# Sensor_Al_Fatih_Multiplekser_Baru.net
KiCad netlist of a schematic drawn in EAGLE
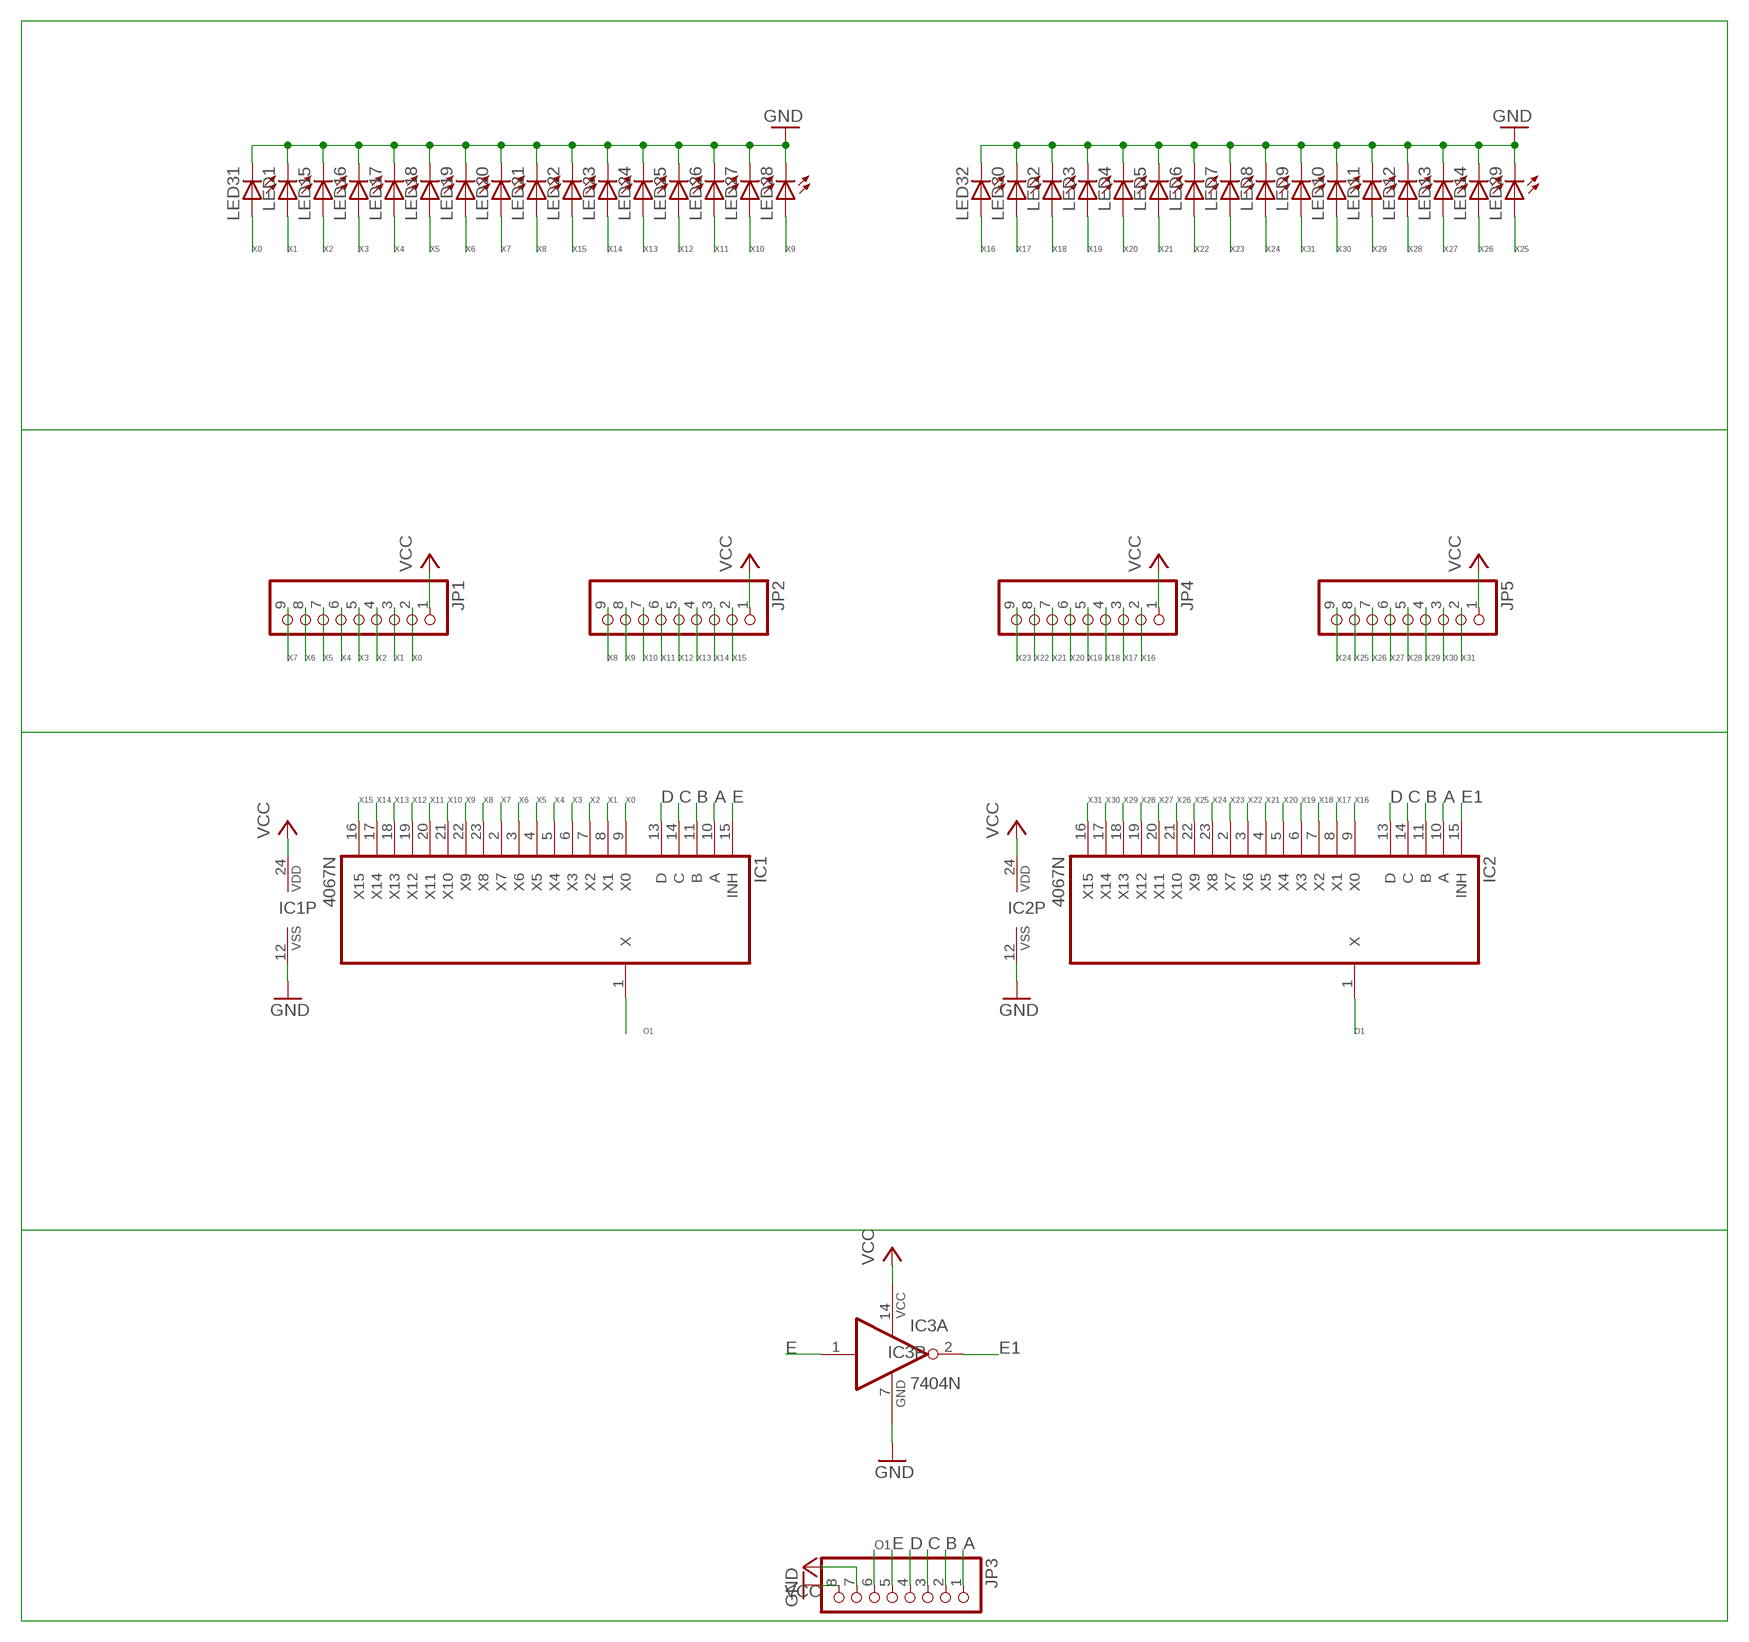
[diagram p0: schematic, sheet 1]

(export (version "E")
  (design (tool "Eeschema 10.0.6"))
  (components
    (comp (ref "IC1")
      (value "4067N")
      (footprint "eagle-import:DIL24-6")
      (libsource (lib "eagle-import") (part "4067N"))
    )
    (comp (ref "IC2")
      (value "4067N")
      (footprint "eagle-import:DIL24-6")
      (libsource (lib "eagle-import") (part "4067N"))
    )
    (comp (ref "IC3")
      (value "7404N")
      (footprint "eagle-import:DIL14")
      (libsource (lib "eagle-import") (part "7404N"))
    )
    (comp (ref "JP1")
      (value "PINHD-1X9")
      (footprint "eagle-import:1X09")
      (libsource (lib "eagle-import") (part "PINHD-1X9"))
    )
    (comp (ref "JP2")
      (value "PINHD-1X9")
      (footprint "eagle-import:1X09")
      (libsource (lib "eagle-import") (part "PINHD-1X9"))
    )
    (comp (ref "JP3")
      (value "PINHD-1X8")
      (footprint "eagle-import:1X08")
      (libsource (lib "eagle-import") (part "PINHD-1X8"))
    )
    (comp (ref "JP4")
      (value "PINHD-1X9")
      (footprint "eagle-import:1X09")
      (libsource (lib "eagle-import") (part "PINHD-1X9"))
    )
    (comp (ref "JP5")
      (value "PINHD-1X9")
      (footprint "eagle-import:1X09")
      (libsource (lib "eagle-import") (part "PINHD-1X9"))
    )
    (comp (ref "LED1")
      (value "LED3MM")
      (footprint "eagle-import:LED3MM")
      (libsource (lib "eagle-import") (part "LED3MM"))
    )
    (comp (ref "LED2")
      (value "LED3MM")
      (footprint "eagle-import:LED3MM")
      (libsource (lib "eagle-import") (part "LED3MM"))
    )
    (comp (ref "LED3")
      (value "LED3MM")
      (footprint "eagle-import:LED3MM")
      (libsource (lib "eagle-import") (part "LED3MM"))
    )
    (comp (ref "LED4")
      (value "LED3MM")
      (footprint "eagle-import:LED3MM")
      (libsource (lib "eagle-import") (part "LED3MM"))
    )
    (comp (ref "LED5")
      (value "LED3MM")
      (footprint "eagle-import:LED3MM")
      (libsource (lib "eagle-import") (part "LED3MM"))
    )
    (comp (ref "LED6")
      (value "LED3MM")
      (footprint "eagle-import:LED3MM")
      (libsource (lib "eagle-import") (part "LED3MM"))
    )
    (comp (ref "LED7")
      (value "LED3MM")
      (footprint "eagle-import:LED3MM")
      (libsource (lib "eagle-import") (part "LED3MM"))
    )
    (comp (ref "LED8")
      (value "LED3MM")
      (footprint "eagle-import:LED3MM")
      (libsource (lib "eagle-import") (part "LED3MM"))
    )
    (comp (ref "LED9")
      (value "LED3MM")
      (footprint "eagle-import:LED3MM")
      (libsource (lib "eagle-import") (part "LED3MM"))
    )
    (comp (ref "LED10")
      (value "LED3MM")
      (footprint "eagle-import:LED3MM")
      (libsource (lib "eagle-import") (part "LED3MM"))
    )
    (comp (ref "LED11")
      (value "LED3MM")
      (footprint "eagle-import:LED3MM")
      (libsource (lib "eagle-import") (part "LED3MM"))
    )
    (comp (ref "LED12")
      (value "LED3MM")
      (footprint "eagle-import:LED3MM")
      (libsource (lib "eagle-import") (part "LED3MM"))
    )
    (comp (ref "LED13")
      (value "LED3MM")
      (footprint "eagle-import:LED3MM")
      (libsource (lib "eagle-import") (part "LED3MM"))
    )
    (comp (ref "LED14")
      (value "LED3MM")
      (footprint "eagle-import:LED3MM")
      (libsource (lib "eagle-import") (part "LED3MM"))
    )
    (comp (ref "LED15")
      (value "LED3MM")
      (footprint "eagle-import:LED3MM")
      (libsource (lib "eagle-import") (part "LED3MM"))
    )
    (comp (ref "LED16")
      (value "LED3MM")
      (footprint "eagle-import:LED3MM")
      (libsource (lib "eagle-import") (part "LED3MM"))
    )
    (comp (ref "LED17")
      (value "LED3MM")
      (footprint "eagle-import:LED3MM")
      (libsource (lib "eagle-import") (part "LED3MM"))
    )
    (comp (ref "LED18")
      (value "LED3MM")
      (footprint "eagle-import:LED3MM")
      (libsource (lib "eagle-import") (part "LED3MM"))
    )
    (comp (ref "LED19")
      (value "LED3MM")
      (footprint "eagle-import:LED3MM")
      (libsource (lib "eagle-import") (part "LED3MM"))
    )
    (comp (ref "LED20")
      (value "LED3MM")
      (footprint "eagle-import:LED3MM")
      (libsource (lib "eagle-import") (part "LED3MM"))
    )
    (comp (ref "LED21")
      (value "LED3MM")
      (footprint "eagle-import:LED3MM")
      (libsource (lib "eagle-import") (part "LED3MM"))
    )
    (comp (ref "LED22")
      (value "LED3MM")
      (footprint "eagle-import:LED3MM")
      (libsource (lib "eagle-import") (part "LED3MM"))
    )
    (comp (ref "LED23")
      (value "LED3MM")
      (footprint "eagle-import:LED3MM")
      (libsource (lib "eagle-import") (part "LED3MM"))
    )
    (comp (ref "LED24")
      (value "LED3MM")
      (footprint "eagle-import:LED3MM")
      (libsource (lib "eagle-import") (part "LED3MM"))
    )
    (comp (ref "LED25")
      (value "LED3MM")
      (footprint "eagle-import:LED3MM")
      (libsource (lib "eagle-import") (part "LED3MM"))
    )
    (comp (ref "LED26")
      (value "LED3MM")
      (footprint "eagle-import:LED3MM")
      (libsource (lib "eagle-import") (part "LED3MM"))
    )
    (comp (ref "LED27")
      (value "LED3MM")
      (footprint "eagle-import:LED3MM")
      (libsource (lib "eagle-import") (part "LED3MM"))
    )
    (comp (ref "LED28")
      (value "LED3MM")
      (footprint "eagle-import:LED3MM")
      (libsource (lib "eagle-import") (part "LED3MM"))
    )
    (comp (ref "LED29")
      (value "LED3MM")
      (footprint "eagle-import:LED3MM")
      (libsource (lib "eagle-import") (part "LED3MM"))
    )
    (comp (ref "LED30")
      (value "LED3MM")
      (footprint "eagle-import:LED3MM")
      (libsource (lib "eagle-import") (part "LED3MM"))
    )
    (comp (ref "LED31")
      (value "LED3MM")
      (footprint "eagle-import:LED3MM")
      (libsource (lib "eagle-import") (part "LED3MM"))
    )
    (comp (ref "LED32")
      (value "LED3MM")
      (footprint "eagle-import:LED3MM")
      (libsource (lib "eagle-import") (part "LED3MM"))
    )
  )
  (nets
    (net (code "1") (name "/A") (class "Default")
      (node (ref "IC1") (pin "10") (pinfunction "A_10") (pintype "input"))
      (node (ref "IC2") (pin "10") (pinfunction "A_10") (pintype "input"))
      (node (ref "JP3") (pin "1") (pinfunction "1_1") (pintype "passive"))
    )
    (net (code "2") (name "/B") (class "Default")
      (node (ref "IC1") (pin "11") (pinfunction "B_11") (pintype "input"))
      (node (ref "IC2") (pin "11") (pinfunction "B_11") (pintype "input"))
      (node (ref "JP3") (pin "2") (pinfunction "2_2") (pintype "passive"))
    )
    (net (code "3") (name "/C") (class "Default")
      (node (ref "IC1") (pin "14") (pinfunction "C_14") (pintype "input"))
      (node (ref "IC2") (pin "14") (pinfunction "C_14") (pintype "input"))
      (node (ref "JP3") (pin "3") (pinfunction "3_3") (pintype "passive"))
    )
    (net (code "4") (name "/D") (class "Default")
      (node (ref "IC1") (pin "13") (pinfunction "D_13") (pintype "input"))
      (node (ref "IC2") (pin "13") (pinfunction "D_13") (pintype "input"))
      (node (ref "JP3") (pin "4") (pinfunction "4_4") (pintype "passive"))
    )
    (net (code "5") (name "/E") (class "Default")
      (node (ref "IC1") (pin "15") (pinfunction "INH_15") (pintype "input"))
      (node (ref "IC3") (pin "1") (pinfunction "I_1") (pintype "input"))
      (node (ref "JP3") (pin "5") (pinfunction "5_5") (pintype "passive"))
    )
    (net (code "6") (name "/E1") (class "Default")
      (node (ref "IC2") (pin "15") (pinfunction "INH_15") (pintype "input"))
      (node (ref "IC3") (pin "2") (pinfunction "O_2") (pintype "output"))
    )
    (net (code "7") (name "/O1") (class "Default")
      (node (ref "IC1") (pin "1") (pinfunction "X_1") (pintype "output"))
      (node (ref "IC2") (pin "1") (pinfunction "X_1") (pintype "output"))
      (node (ref "JP3") (pin "6") (pinfunction "6_6") (pintype "passive"))
    )
    (net (code "8") (name "/X0") (class "Default")
      (node (ref "IC1") (pin "9") (pinfunction "X0_9") (pintype "input"))
      (node (ref "JP1") (pin "2") (pinfunction "2_2") (pintype "passive"))
      (node (ref "LED31") (pin "A") (pinfunction "A_A") (pintype "passive"))
    )
    (net (code "9") (name "/X1") (class "Default")
      (node (ref "IC1") (pin "8") (pinfunction "X1_8") (pintype "input"))
      (node (ref "JP1") (pin "3") (pinfunction "3_3") (pintype "passive"))
      (node (ref "LED1") (pin "A") (pinfunction "A_A") (pintype "passive"))
    )
    (net (code "10") (name "/X2") (class "Default")
      (node (ref "IC1") (pin "7") (pinfunction "X2_7") (pintype "input"))
      (node (ref "JP1") (pin "4") (pinfunction "4_4") (pintype "passive"))
      (node (ref "LED15") (pin "A") (pinfunction "A_A") (pintype "passive"))
    )
    (net (code "11") (name "/X3") (class "Default")
      (node (ref "IC1") (pin "6") (pinfunction "X3_6") (pintype "input"))
      (node (ref "JP1") (pin "5") (pinfunction "5_5") (pintype "passive"))
      (node (ref "LED16") (pin "A") (pinfunction "A_A") (pintype "passive"))
    )
    (net (code "12") (name "/X4") (class "Default")
      (node (ref "IC1") (pin "5") (pinfunction "X4_5") (pintype "input"))
      (node (ref "JP1") (pin "6") (pinfunction "6_6") (pintype "passive"))
      (node (ref "LED17") (pin "A") (pinfunction "A_A") (pintype "passive"))
    )
    (net (code "13") (name "/X5") (class "Default")
      (node (ref "IC1") (pin "4") (pinfunction "X5_4") (pintype "input"))
      (node (ref "JP1") (pin "7") (pinfunction "7_7") (pintype "passive"))
      (node (ref "LED18") (pin "A") (pinfunction "A_A") (pintype "passive"))
    )
    (net (code "14") (name "/X6") (class "Default")
      (node (ref "IC1") (pin "3") (pinfunction "X6_3") (pintype "input"))
      (node (ref "JP1") (pin "8") (pinfunction "8_8") (pintype "passive"))
      (node (ref "LED19") (pin "A") (pinfunction "A_A") (pintype "passive"))
    )
    (net (code "15") (name "/X7") (class "Default")
      (node (ref "IC1") (pin "2") (pinfunction "X7_2") (pintype "input"))
      (node (ref "JP1") (pin "9") (pinfunction "9_9") (pintype "passive"))
      (node (ref "LED20") (pin "A") (pinfunction "A_A") (pintype "passive"))
    )
    (net (code "16") (name "/X8") (class "Default")
      (node (ref "IC1") (pin "23") (pinfunction "X8_23") (pintype "input"))
      (node (ref "JP2") (pin "9") (pinfunction "9_9") (pintype "passive"))
      (node (ref "LED21") (pin "A") (pinfunction "A_A") (pintype "passive"))
    )
    (net (code "17") (name "/X9") (class "Default")
      (node (ref "IC1") (pin "22") (pinfunction "X9_22") (pintype "input"))
      (node (ref "JP2") (pin "8") (pinfunction "8_8") (pintype "passive"))
      (node (ref "LED28") (pin "A") (pinfunction "A_A") (pintype "passive"))
    )
    (net (code "18") (name "/X10") (class "Default")
      (node (ref "IC1") (pin "21") (pinfunction "X10_21") (pintype "input"))
      (node (ref "JP2") (pin "7") (pinfunction "7_7") (pintype "passive"))
      (node (ref "LED27") (pin "A") (pinfunction "A_A") (pintype "passive"))
    )
    (net (code "19") (name "/X11") (class "Default")
      (node (ref "IC1") (pin "20") (pinfunction "X11_20") (pintype "input"))
      (node (ref "JP2") (pin "6") (pinfunction "6_6") (pintype "passive"))
      (node (ref "LED26") (pin "A") (pinfunction "A_A") (pintype "passive"))
    )
    (net (code "20") (name "/X12") (class "Default")
      (node (ref "IC1") (pin "19") (pinfunction "X12_19") (pintype "input"))
      (node (ref "JP2") (pin "5") (pinfunction "5_5") (pintype "passive"))
      (node (ref "LED25") (pin "A") (pinfunction "A_A") (pintype "passive"))
    )
    (net (code "21") (name "/X13") (class "Default")
      (node (ref "IC1") (pin "18") (pinfunction "X13_18") (pintype "input"))
      (node (ref "JP2") (pin "4") (pinfunction "4_4") (pintype "passive"))
      (node (ref "LED24") (pin "A") (pinfunction "A_A") (pintype "passive"))
    )
    (net (code "22") (name "/X14") (class "Default")
      (node (ref "IC1") (pin "17") (pinfunction "X14_17") (pintype "input"))
      (node (ref "JP2") (pin "3") (pinfunction "3_3") (pintype "passive"))
      (node (ref "LED23") (pin "A") (pinfunction "A_A") (pintype "passive"))
    )
    (net (code "23") (name "/X15") (class "Default")
      (node (ref "IC1") (pin "16") (pinfunction "X15_16") (pintype "input"))
      (node (ref "JP2") (pin "2") (pinfunction "2_2") (pintype "passive"))
      (node (ref "LED22") (pin "A") (pinfunction "A_A") (pintype "passive"))
    )
    (net (code "24") (name "/X16") (class "Default")
      (node (ref "IC2") (pin "9") (pinfunction "X0_9") (pintype "input"))
      (node (ref "JP4") (pin "2") (pinfunction "2_2") (pintype "passive"))
      (node (ref "LED32") (pin "A") (pinfunction "A_A") (pintype "passive"))
    )
    (net (code "25") (name "/X17") (class "Default")
      (node (ref "IC2") (pin "8") (pinfunction "X1_8") (pintype "input"))
      (node (ref "JP4") (pin "3") (pinfunction "3_3") (pintype "passive"))
      (node (ref "LED30") (pin "A") (pinfunction "A_A") (pintype "passive"))
    )
    (net (code "26") (name "/X18") (class "Default")
      (node (ref "IC2") (pin "7") (pinfunction "X2_7") (pintype "input"))
      (node (ref "JP4") (pin "4") (pinfunction "4_4") (pintype "passive"))
      (node (ref "LED2") (pin "A") (pinfunction "A_A") (pintype "passive"))
    )
    (net (code "27") (name "/X19") (class "Default")
      (node (ref "IC2") (pin "6") (pinfunction "X3_6") (pintype "input"))
      (node (ref "JP4") (pin "5") (pinfunction "5_5") (pintype "passive"))
      (node (ref "LED3") (pin "A") (pinfunction "A_A") (pintype "passive"))
    )
    (net (code "28") (name "/X20") (class "Default")
      (node (ref "IC2") (pin "5") (pinfunction "X4_5") (pintype "input"))
      (node (ref "JP4") (pin "6") (pinfunction "6_6") (pintype "passive"))
      (node (ref "LED4") (pin "A") (pinfunction "A_A") (pintype "passive"))
    )
    (net (code "29") (name "/X21") (class "Default")
      (node (ref "IC2") (pin "4") (pinfunction "X5_4") (pintype "input"))
      (node (ref "JP4") (pin "7") (pinfunction "7_7") (pintype "passive"))
      (node (ref "LED5") (pin "A") (pinfunction "A_A") (pintype "passive"))
    )
    (net (code "30") (name "/X22") (class "Default")
      (node (ref "IC2") (pin "3") (pinfunction "X6_3") (pintype "input"))
      (node (ref "JP4") (pin "8") (pinfunction "8_8") (pintype "passive"))
      (node (ref "LED6") (pin "A") (pinfunction "A_A") (pintype "passive"))
    )
    (net (code "31") (name "/X23") (class "Default")
      (node (ref "IC2") (pin "2") (pinfunction "X7_2") (pintype "input"))
      (node (ref "JP4") (pin "9") (pinfunction "9_9") (pintype "passive"))
      (node (ref "LED7") (pin "A") (pinfunction "A_A") (pintype "passive"))
    )
    (net (code "32") (name "/X24") (class "Default")
      (node (ref "IC2") (pin "23") (pinfunction "X8_23") (pintype "input"))
      (node (ref "JP5") (pin "9") (pinfunction "9_9") (pintype "passive"))
      (node (ref "LED8") (pin "A") (pinfunction "A_A") (pintype "passive"))
    )
    (net (code "33") (name "/X25") (class "Default")
      (node (ref "IC2") (pin "22") (pinfunction "X9_22") (pintype "input"))
      (node (ref "JP5") (pin "8") (pinfunction "8_8") (pintype "passive"))
      (node (ref "LED29") (pin "A") (pinfunction "A_A") (pintype "passive"))
    )
    (net (code "34") (name "/X26") (class "Default")
      (node (ref "IC2") (pin "21") (pinfunction "X10_21") (pintype "input"))
      (node (ref "JP5") (pin "7") (pinfunction "7_7") (pintype "passive"))
      (node (ref "LED14") (pin "A") (pinfunction "A_A") (pintype "passive"))
    )
    (net (code "35") (name "/X27") (class "Default")
      (node (ref "IC2") (pin "20") (pinfunction "X11_20") (pintype "input"))
      (node (ref "JP5") (pin "6") (pinfunction "6_6") (pintype "passive"))
      (node (ref "LED13") (pin "A") (pinfunction "A_A") (pintype "passive"))
    )
    (net (code "36") (name "/X28") (class "Default")
      (node (ref "IC2") (pin "19") (pinfunction "X12_19") (pintype "input"))
      (node (ref "JP5") (pin "5") (pinfunction "5_5") (pintype "passive"))
      (node (ref "LED12") (pin "A") (pinfunction "A_A") (pintype "passive"))
    )
    (net (code "37") (name "/X29") (class "Default")
      (node (ref "IC2") (pin "18") (pinfunction "X13_18") (pintype "input"))
      (node (ref "JP5") (pin "4") (pinfunction "4_4") (pintype "passive"))
      (node (ref "LED11") (pin "A") (pinfunction "A_A") (pintype "passive"))
    )
    (net (code "38") (name "/X30") (class "Default")
      (node (ref "IC2") (pin "17") (pinfunction "X14_17") (pintype "input"))
      (node (ref "JP5") (pin "3") (pinfunction "3_3") (pintype "passive"))
      (node (ref "LED10") (pin "A") (pinfunction "A_A") (pintype "passive"))
    )
    (net (code "39") (name "/X31") (class "Default")
      (node (ref "IC2") (pin "16") (pinfunction "X15_16") (pintype "input"))
      (node (ref "JP5") (pin "2") (pinfunction "2_2") (pintype "passive"))
      (node (ref "LED9") (pin "A") (pinfunction "A_A") (pintype "passive"))
    )
    (net (code "40") (name "GND") (class "Default")
      (node (ref "IC1") (pin "12") (pinfunction "VSS_12") (pintype "power_in"))
      (node (ref "IC2") (pin "12") (pinfunction "VSS_12") (pintype "power_in"))
      (node (ref "IC3") (pin "7") (pinfunction "GND_7") (pintype "power_in"))
      (node (ref "JP3") (pin "8") (pinfunction "8_8") (pintype "passive"))
      (node (ref "LED1") (pin "K") (pinfunction "C_K") (pintype "passive"))
      (node (ref "LED10") (pin "K") (pinfunction "C_K") (pintype "passive"))
      (node (ref "LED11") (pin "K") (pinfunction "C_K") (pintype "passive"))
      (node (ref "LED12") (pin "K") (pinfunction "C_K") (pintype "passive"))
      (node (ref "LED13") (pin "K") (pinfunction "C_K") (pintype "passive"))
      (node (ref "LED14") (pin "K") (pinfunction "C_K") (pintype "passive"))
      (node (ref "LED15") (pin "K") (pinfunction "C_K") (pintype "passive"))
      (node (ref "LED16") (pin "K") (pinfunction "C_K") (pintype "passive"))
      (node (ref "LED17") (pin "K") (pinfunction "C_K") (pintype "passive"))
      (node (ref "LED18") (pin "K") (pinfunction "C_K") (pintype "passive"))
      (node (ref "LED19") (pin "K") (pinfunction "C_K") (pintype "passive"))
      (node (ref "LED2") (pin "K") (pinfunction "C_K") (pintype "passive"))
      (node (ref "LED20") (pin "K") (pinfunction "C_K") (pintype "passive"))
      (node (ref "LED21") (pin "K") (pinfunction "C_K") (pintype "passive"))
      (node (ref "LED22") (pin "K") (pinfunction "C_K") (pintype "passive"))
      (node (ref "LED23") (pin "K") (pinfunction "C_K") (pintype "passive"))
      (node (ref "LED24") (pin "K") (pinfunction "C_K") (pintype "passive"))
      (node (ref "LED25") (pin "K") (pinfunction "C_K") (pintype "passive"))
      (node (ref "LED26") (pin "K") (pinfunction "C_K") (pintype "passive"))
      (node (ref "LED27") (pin "K") (pinfunction "C_K") (pintype "passive"))
      (node (ref "LED28") (pin "K") (pinfunction "C_K") (pintype "passive"))
      (node (ref "LED29") (pin "K") (pinfunction "C_K") (pintype "passive"))
      (node (ref "LED3") (pin "K") (pinfunction "C_K") (pintype "passive"))
      (node (ref "LED30") (pin "K") (pinfunction "C_K") (pintype "passive"))
      (node (ref "LED31") (pin "K") (pinfunction "C_K") (pintype "passive"))
      (node (ref "LED32") (pin "K") (pinfunction "C_K") (pintype "passive"))
      (node (ref "LED4") (pin "K") (pinfunction "C_K") (pintype "passive"))
      (node (ref "LED5") (pin "K") (pinfunction "C_K") (pintype "passive"))
      (node (ref "LED6") (pin "K") (pinfunction "C_K") (pintype "passive"))
      (node (ref "LED7") (pin "K") (pinfunction "C_K") (pintype "passive"))
      (node (ref "LED8") (pin "K") (pinfunction "C_K") (pintype "passive"))
      (node (ref "LED9") (pin "K") (pinfunction "C_K") (pintype "passive"))
    )
    (net (code "41") (name "VCC") (class "Default")
      (node (ref "IC1") (pin "24") (pinfunction "VDD_24") (pintype "power_in"))
      (node (ref "IC2") (pin "24") (pinfunction "VDD_24") (pintype "power_in"))
      (node (ref "IC3") (pin "14") (pinfunction "VCC_14") (pintype "power_in"))
      (node (ref "JP1") (pin "1") (pinfunction "1_1") (pintype "passive"))
      (node (ref "JP2") (pin "1") (pinfunction "1_1") (pintype "passive"))
      (node (ref "JP3") (pin "7") (pinfunction "7_7") (pintype "passive"))
      (node (ref "JP4") (pin "1") (pinfunction "1_1") (pintype "passive"))
      (node (ref "JP5") (pin "1") (pinfunction "1_1") (pintype "passive"))
    )
  )
)
